# smart_ice_shield_pcb.net
KiCad netlist of a schematic drawn in EAGLE
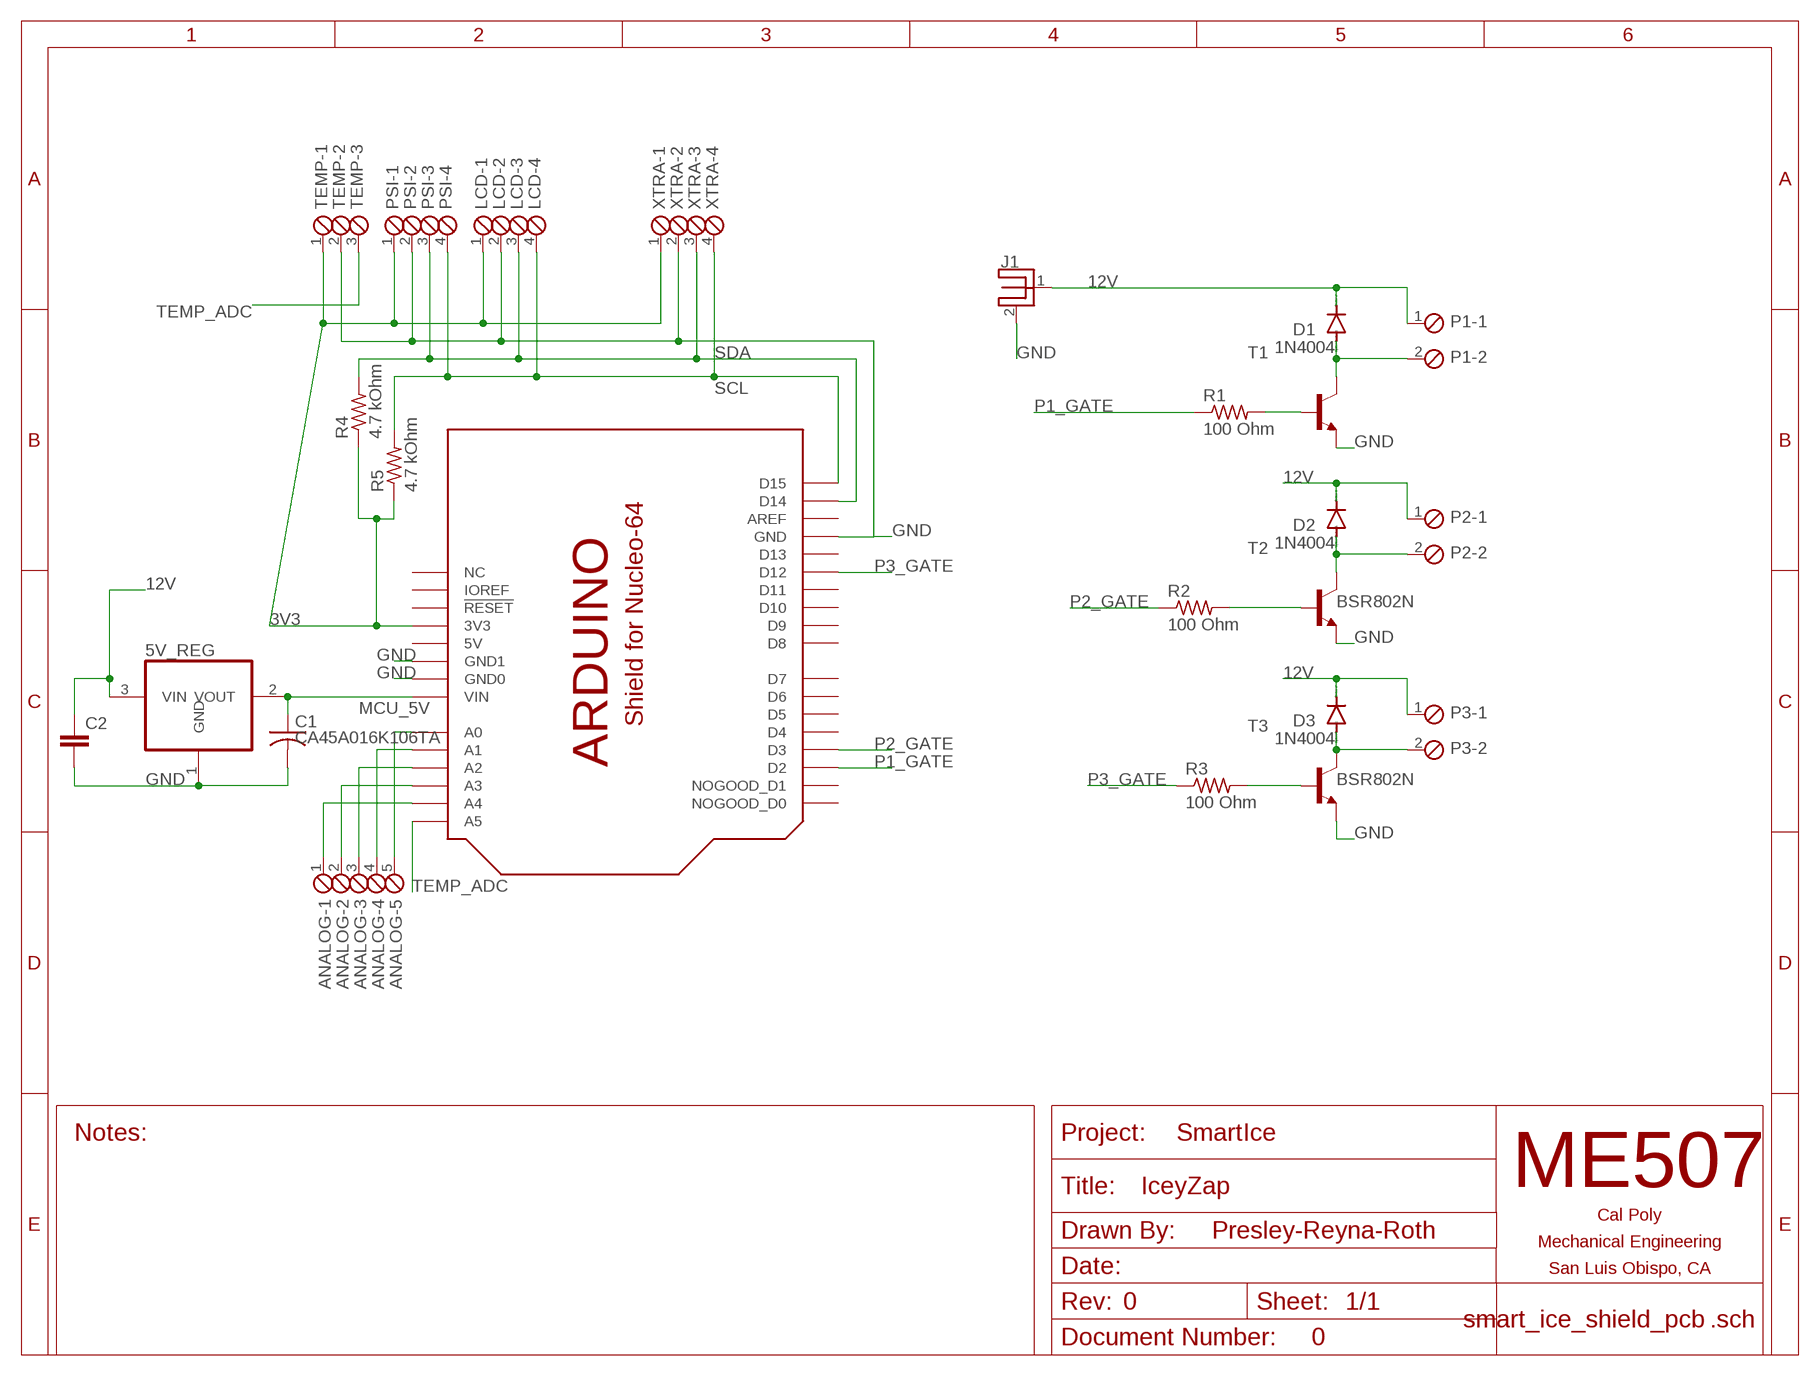
[diagram p0: schematic, sheet 1]

(export (version "E")
  (design (tool "Eeschema 10.0.6"))
  (components
    (comp (ref "5V_REG")
      (value "LT1117CST")
      (footprint "eagle-import:SOT223")
      (fields (field (name "MPN") "REG1117"))
      (libsource (lib "eagle-import") (part "REG1117"))
    )
    (comp (ref "ANALOG")
      (value "SCREWTERM_5P_254")
      (footprint "eagle-import:5POL254")
      (libsource (lib "eagle-import") (part "SCREWTERM_5P_254"))
    )
    (comp (ref "C1")
      (value "CA45A016K106TA")
      (footprint "eagle-import:C1206")
      (libsource (lib "eagle-import") (part "C-USC1206"))
    )
    (comp (ref "C2")
      (value "C-EU025-025X050")
      (footprint "eagle-import:C025-025X050")
      (libsource (lib "eagle-import") (part "C-EU025-025X050"))
    )
    (comp (ref "D1")
      (value "1N4004")
      (footprint "eagle-import:DO41-10")
      (libsource (lib "eagle-import") (part "1N4004"))
    )
    (comp (ref "D2")
      (value "1N4004")
      (footprint "eagle-import:DO41-10")
      (libsource (lib "eagle-import") (part "1N4004"))
    )
    (comp (ref "D3")
      (value "1N4004")
      (footprint "eagle-import:DO41-10")
      (libsource (lib "eagle-import") (part "1N4004"))
    )
    (comp (ref "J1")
      (value "BARREL5.5X2.1PJ-037A")
      (footprint "eagle-import:PJ-037A")
      (fields (field (name "MPN") "PJ-037A"))
      (libsource (lib "eagle-import") (part "BARRELPJ-037A5.5X2.1"))
    )
    (comp (ref "LCD")
      (value "SCREWTERM_4P_254")
      (footprint "eagle-import:4POL254")
      (libsource (lib "eagle-import") (part "SCREWTERM_4P_254"))
    )
    (comp (ref "P1")
      (value "SCREWTERM_2P_381")
      (footprint "eagle-import:2POL381")
      (libsource (lib "eagle-import") (part "SCREWTERM_2P_381"))
    )
    (comp (ref "P2")
      (value "SCREWTERM_2P_381")
      (footprint "eagle-import:2POL381")
      (libsource (lib "eagle-import") (part "SCREWTERM_2P_381"))
    )
    (comp (ref "P3")
      (value "SCREWTERM_2P_381")
      (footprint "eagle-import:2POL381")
      (libsource (lib "eagle-import") (part "SCREWTERM_2P_381"))
    )
    (comp (ref "PSI")
      (value "SCREWTERM_4P_254")
      (footprint "eagle-import:4POL254")
      (libsource (lib "eagle-import") (part "SCREWTERM_4P_254"))
    )
    (comp (ref "R1")
      (value "100 Ohm")
      (footprint "eagle-import:R0805")
      (libsource (lib "eagle-import") (part "R-US_R0805"))
    )
    (comp (ref "R2")
      (value "100 Ohm")
      (footprint "eagle-import:R0805")
      (libsource (lib "eagle-import") (part "R-US_R0805"))
    )
    (comp (ref "R3")
      (value "100 Ohm")
      (footprint "eagle-import:R0805")
      (libsource (lib "eagle-import") (part "R-US_R0805"))
    )
    (comp (ref "R4")
      (value "4.7 kOhm")
      (footprint "eagle-import:R0805")
      (libsource (lib "eagle-import") (part "R-US_R0805"))
    )
    (comp (ref "R5")
      (value "4.7 kOhm")
      (footprint "eagle-import:R0805")
      (libsource (lib "eagle-import") (part "R-US_R0805"))
    )
    (comp (ref "T1")
      (value "BSR802N")
      (footprint "eagle-import:SOT23-BEC")
      (libsource (lib "eagle-import") (part "-NPN-SOT23-BECBSR13"))
    )
    (comp (ref "T2")
      (value "BSR802N")
      (footprint "eagle-import:SOT23-BEC")
      (libsource (lib "eagle-import") (part "-NPN-SOT23-BECBSR13"))
    )
    (comp (ref "T3")
      (value "BSR802N")
      (footprint "eagle-import:SOT23-BEC")
      (libsource (lib "eagle-import") (part "-NPN-SOT23-BECBSR13"))
    )
    (comp (ref "TEMP")
      (value "SCREWTERM_3P_254")
      (footprint "eagle-import:3POL254")
      (libsource (lib "eagle-import") (part "SCREWTERM_3P_254"))
    )
    (comp (ref "U$1")
      (value "SHIELD_FOR_NUCLE0_64_SHORT")
      (footprint "eagle-import:SHIELD_FOR_NUCLEO_64_SHORT")
      (libsource (lib "eagle-import") (part "SHIELD_FOR_NUCLE0_64_SHORT"))
    )
    (comp (ref "XTRA")
      (value "SCREWTERM_4P_254")
      (footprint "eagle-import:4POL254")
      (libsource (lib "eagle-import") (part "SCREWTERM_4P_254"))
    )
  )
  (nets
    (net (code "1") (name "/3V3") (class "Default")
      (node (ref "LCD") (pin "1") (pinfunction "1_1") (pintype "passive"))
      (node (ref "PSI") (pin "1") (pinfunction "1_1") (pintype "passive"))
      (node (ref "R4") (pin "1") (pinfunction "1_1") (pintype "passive"))
      (node (ref "R5") (pin "1") (pinfunction "1_1") (pintype "passive"))
      (node (ref "TEMP") (pin "1") (pinfunction "1_1") (pintype "passive"))
      (node (ref "U$1") (pin "3V") (pinfunction "3V3_3V") (pintype "power_in"))
      (node (ref "XTRA") (pin "1") (pinfunction "1_1") (pintype "passive"))
    )
    (net (code "2") (name "/5V") (class "Default")
      (node (ref "U$1") (pin "5V") (pinfunction "5V_5V") (pintype "power_in"))
    )
    (net (code "3") (name "/12V") (class "Default")
      (node (ref "5V_REG") (pin "3") (pinfunction "VIN_3") (pintype "input"))
      (node (ref "C2") (pin "1") (pinfunction "1_1") (pintype "passive"))
      (node (ref "D1") (pin "C") (pinfunction "C_C") (pintype "passive"))
      (node (ref "D2") (pin "C") (pinfunction "C_C") (pintype "passive"))
      (node (ref "D3") (pin "C") (pinfunction "C_C") (pintype "passive"))
      (node (ref "J1") (pin "1") (pinfunction "CENTER_1") (pintype "bidirectional"))
      (node (ref "P1") (pin "1") (pinfunction "1_1") (pintype "passive"))
      (node (ref "P2") (pin "1") (pinfunction "1_1") (pintype "passive"))
      (node (ref "P3") (pin "1") (pinfunction "1_1") (pintype "passive"))
    )
    (net (code "4") (name "/GND") (class "Default")
      (node (ref "5V_REG") (pin "1") (pinfunction "GND_1") (pintype "power_in"))
      (node (ref "C1") (pin "2") (pinfunction "2_2") (pintype "passive"))
      (node (ref "C2") (pin "2") (pinfunction "2_2") (pintype "passive"))
      (node (ref "J1") (pin "2") (pinfunction "BARREL_2") (pintype "bidirectional"))
      (node (ref "LCD") (pin "2") (pinfunction "1_2") (pintype "passive"))
      (node (ref "PSI") (pin "2") (pinfunction "1_2") (pintype "passive"))
      (node (ref "T1") (pin "E") (pinfunction "E_E") (pintype "passive"))
      (node (ref "T2") (pin "E") (pinfunction "E_E") (pintype "passive"))
      (node (ref "T3") (pin "E") (pinfunction "E_E") (pintype "passive"))
      (node (ref "TEMP") (pin "2") (pinfunction "1_2") (pintype "passive"))
      (node (ref "U$1") (pin "GND") (pinfunction "GND_GND") (pintype "power_in"))
      (node (ref "U$1") (pin "GND1") (pinfunction "GND0_GND1") (pintype "power_in"))
      (node (ref "U$1") (pin "GND2") (pinfunction "GND1_GND2") (pintype "power_in"))
      (node (ref "XTRA") (pin "2") (pinfunction "1_2") (pintype "passive"))
    )
    (net (code "5") (name "/MCU_5V") (class "Default")
      (node (ref "5V_REG") (pin "2") (pinfunction "VOUT_2") (pintype "output"))
      (node (ref "C1") (pin "1") (pinfunction "1_1") (pintype "passive"))
      (node (ref "U$1") (pin "VIN") (pinfunction "VIN_VIN") (pintype "power_in"))
    )
    (net (code "6") (name "/P1_GATE") (class "Default")
      (node (ref "R1") (pin "1") (pinfunction "1_1") (pintype "passive"))
      (node (ref "U$1") (pin "D2") (pinfunction "D2_D2") (pintype "bidirectional"))
    )
    (net (code "7") (name "/P2_GATE") (class "Default")
      (node (ref "R2") (pin "1") (pinfunction "1_1") (pintype "passive"))
      (node (ref "U$1") (pin "D3") (pinfunction "D3_D3") (pintype "bidirectional"))
    )
    (net (code "8") (name "/P3_GATE") (class "Default")
      (node (ref "R3") (pin "1") (pinfunction "1_1") (pintype "passive"))
      (node (ref "U$1") (pin "D12") (pinfunction "D12_D12") (pintype "bidirectional"))
    )
    (net (code "9") (name "/SCL") (class "Default")
      (node (ref "LCD") (pin "4") (pinfunction "1_4") (pintype "passive"))
      (node (ref "PSI") (pin "4") (pinfunction "1_4") (pintype "passive"))
      (node (ref "R5") (pin "2") (pinfunction "2_2") (pintype "passive"))
      (node (ref "U$1") (pin "D15") (pinfunction "D15_D15") (pintype "bidirectional"))
      (node (ref "XTRA") (pin "4") (pinfunction "1_4") (pintype "passive"))
    )
    (net (code "10") (name "/SDA") (class "Default")
      (node (ref "LCD") (pin "3") (pinfunction "1_3") (pintype "passive"))
      (node (ref "PSI") (pin "3") (pinfunction "1_3") (pintype "passive"))
      (node (ref "R4") (pin "2") (pinfunction "2_2") (pintype "passive"))
      (node (ref "U$1") (pin "D14") (pinfunction "D14_D14") (pintype "bidirectional"))
      (node (ref "XTRA") (pin "3") (pinfunction "1_3") (pintype "passive"))
    )
    (net (code "11") (name "/TEMP_ADC") (class "Default")
      (node (ref "TEMP") (pin "3") (pinfunction "1_3") (pintype "passive"))
      (node (ref "U$1") (pin "A5") (pinfunction "A5_A5") (pintype "bidirectional"))
    )
    (net (code "12") (name "Net-(ANALOG-Pad1)") (class "Default")
      (node (ref "ANALOG") (pin "1") (pinfunction "1_1") (pintype "passive"))
      (node (ref "U$1") (pin "A4") (pinfunction "A4_A4") (pintype "bidirectional"))
    )
    (net (code "13") (name "Net-(ANALOGB-1)") (class "Default")
      (node (ref "ANALOG") (pin "2") (pinfunction "1_2") (pintype "passive"))
      (node (ref "U$1") (pin "A3") (pinfunction "A3_A3") (pintype "bidirectional"))
    )
    (net (code "14") (name "Net-(ANALOGC-1)") (class "Default")
      (node (ref "ANALOG") (pin "3") (pinfunction "1_3") (pintype "passive"))
      (node (ref "U$1") (pin "A2") (pinfunction "A2_A2") (pintype "bidirectional"))
    )
    (net (code "15") (name "Net-(ANALOGD-1)") (class "Default")
      (node (ref "ANALOG") (pin "4") (pinfunction "1_4") (pintype "passive"))
      (node (ref "U$1") (pin "A1") (pinfunction "A1_A1") (pintype "bidirectional"))
    )
    (net (code "16") (name "Net-(ANALOGE-1)") (class "Default")
      (node (ref "ANALOG") (pin "5") (pinfunction "1_5") (pintype "passive"))
      (node (ref "U$1") (pin "A0") (pinfunction "A0_A0") (pintype "bidirectional"))
    )
    (net (code "17") (name "Net-(P1B-1)") (class "Default")
      (node (ref "D1") (pin "A") (pinfunction "A_A") (pintype "passive"))
      (node (ref "P1") (pin "2") (pinfunction "1_2") (pintype "passive"))
      (node (ref "T1") (pin "C") (pinfunction "C_C") (pintype "passive"))
    )
    (net (code "18") (name "Net-(P2B-1)") (class "Default")
      (node (ref "D2") (pin "A") (pinfunction "A_A") (pintype "passive"))
      (node (ref "P2") (pin "2") (pinfunction "1_2") (pintype "passive"))
      (node (ref "T2") (pin "C") (pinfunction "C_C") (pintype "passive"))
    )
    (net (code "19") (name "Net-(P3B-1)") (class "Default")
      (node (ref "D3") (pin "A") (pinfunction "A_A") (pintype "passive"))
      (node (ref "P3") (pin "2") (pinfunction "1_2") (pintype "passive"))
      (node (ref "T3") (pin "C") (pinfunction "C_C") (pintype "passive"))
    )
    (net (code "20") (name "Net-(R1-Pad2)") (class "Default")
      (node (ref "R1") (pin "2") (pinfunction "2_2") (pintype "passive"))
      (node (ref "T1") (pin "B") (pinfunction "B_B") (pintype "passive"))
    )
    (net (code "21") (name "Net-(R2-Pad2)") (class "Default")
      (node (ref "R2") (pin "2") (pinfunction "2_2") (pintype "passive"))
      (node (ref "T2") (pin "B") (pinfunction "B_B") (pintype "passive"))
    )
    (net (code "22") (name "Net-(R3-Pad2)") (class "Default")
      (node (ref "R3") (pin "2") (pinfunction "2_2") (pintype "passive"))
      (node (ref "T3") (pin "B") (pinfunction "B_B") (pintype "passive"))
    )
    (net (code "23") (name "unconnected-(U$1-NOGOOD_D0-PadD0)") (class "Default")
      (node (ref "U$1") (pin "D0") (pinfunction "NOGOOD_D0_D0") (pintype "no_connect"))
    )
    (net (code "24") (name "unconnected-(U$1-NOGOOD_D1-PadD1)") (class "Default")
      (node (ref "U$1") (pin "D1") (pinfunction "NOGOOD_D1_D1") (pintype "no_connect"))
    )
    (net (code "25") (name "unconnected-(U$1-PadAREF)") (class "Default")
      (node (ref "U$1") (pin "AREF") (pinfunction "AREF_AREF") (pintype "bidirectional"))
    )
    (net (code "26") (name "unconnected-(U$1-PadD4)") (class "Default")
      (node (ref "U$1") (pin "D4") (pinfunction "D4_D4") (pintype "bidirectional"))
    )
    (net (code "27") (name "unconnected-(U$1-PadD5)") (class "Default")
      (node (ref "U$1") (pin "D5") (pinfunction "D5_D5") (pintype "bidirectional"))
    )
    (net (code "28") (name "unconnected-(U$1-PadD6)") (class "Default")
      (node (ref "U$1") (pin "D6") (pinfunction "D6_D6") (pintype "bidirectional"))
    )
    (net (code "29") (name "unconnected-(U$1-PadD7)") (class "Default")
      (node (ref "U$1") (pin "D7") (pinfunction "D7_D7") (pintype "bidirectional"))
    )
    (net (code "30") (name "unconnected-(U$1-PadD8)") (class "Default")
      (node (ref "U$1") (pin "D8") (pinfunction "D8_D8") (pintype "bidirectional"))
    )
    (net (code "31") (name "unconnected-(U$1-PadD9)") (class "Default")
      (node (ref "U$1") (pin "D9") (pinfunction "D9_D9") (pintype "bidirectional"))
    )
    (net (code "32") (name "unconnected-(U$1-PadD10)") (class "Default")
      (node (ref "U$1") (pin "D10") (pinfunction "D10_D10") (pintype "bidirectional"))
    )
    (net (code "33") (name "unconnected-(U$1-PadD11)") (class "Default")
      (node (ref "U$1") (pin "D11") (pinfunction "D11_D11") (pintype "bidirectional"))
    )
    (net (code "34") (name "unconnected-(U$1-PadD13)") (class "Default")
      (node (ref "U$1") (pin "D13") (pinfunction "D13_D13") (pintype "bidirectional"))
    )
    (net (code "35") (name "unconnected-(U$1-PadIOREF)") (class "Default")
      (node (ref "U$1") (pin "IOREF") (pinfunction "IOREF_IOREF") (pintype "bidirectional"))
    )
    (net (code "36") (name "unconnected-(U$1-PadNC)") (class "Default")
      (node (ref "U$1") (pin "NC") (pinfunction "NC_NC") (pintype "no_connect"))
    )
    (net (code "37") (name "unconnected-(U$1-~{RESET}-PadNRST)") (class "Default")
      (node (ref "U$1") (pin "NRST") (pinfunction "~{RESET}_NRST") (pintype "input"))
    )
  )
)
